# LVDS-Banana.net
KiCad netlist of a schematic drawn in EAGLE
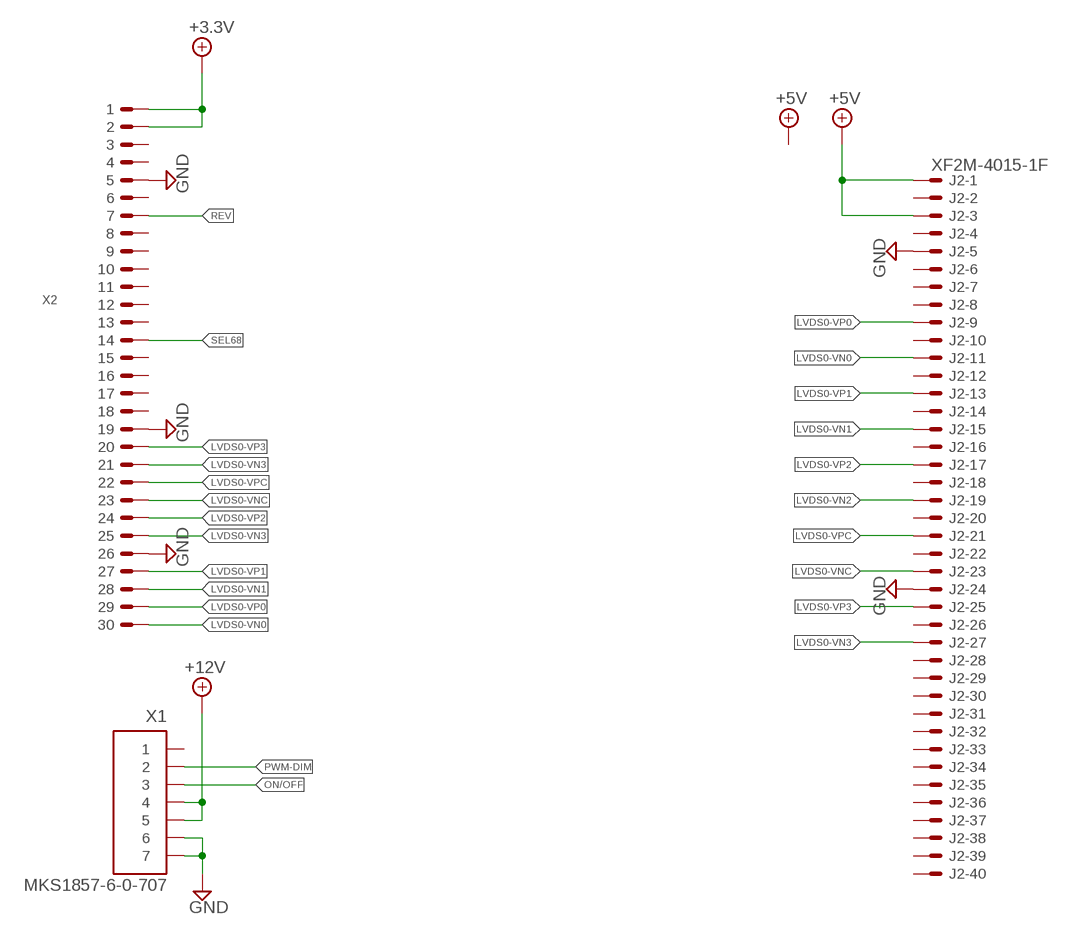
[diagram p0: schematic, sheet 1]

(export (version "E")
  (design (tool "Eeschema 10.0.6"))
  (components
    (comp (ref "J2")
      (value "XF2M-4015-1F")
      (footprint "eagle-import:XF2M-4015-1F")
      (libsource (lib "eagle-import") (part "XF2-40?15-1FM"))
    )
    (comp (ref "X1")
      (value "MKS1857-6-0-707")
      (footprint "eagle-import:MKS1857-6-0-707")
      (libsource (lib "eagle-import") (part "MKS1857-6-0-707"))
    )
    (comp (ref "X2")
      (value "DF14-30P-1.25H")
      (footprint "eagle-import:DF14-30")
      (libsource (lib "eagle-import") (part "DF14-30P-1.25H"))
    )
  )
  (nets
    (net (code "1") (name "+3.3V") (class "Default")
      (node (ref "X2") (pin "1") (pinfunction "1_1") (pintype "passive"))
      (node (ref "X2") (pin "2") (pinfunction "2_2") (pintype "passive"))
    )
    (net (code "2") (name "+5V") (class "Default")
      (node (ref "J2") (pin "1") (pinfunction "MSV_1") (pintype "passive"))
      (node (ref "J2") (pin "3") (pinfunction "MS_3") (pintype "passive"))
    )
    (net (code "3") (name "+12V") (class "Default")
      (node (ref "X1") (pin "4") (pinfunction "4_4") (pintype "input"))
      (node (ref "X1") (pin "5") (pinfunction "5_5") (pintype "input"))
    )
    (net (code "4") (name "GND") (class "Default")
      (node (ref "J2") (pin "24") (pinfunction "MS_24") (pintype "passive"))
      (node (ref "J2") (pin "5") (pinfunction "MS_5") (pintype "passive"))
      (node (ref "X1") (pin "6") (pinfunction "6_6") (pintype "input"))
      (node (ref "X1") (pin "7") (pinfunction "7_7") (pintype "input"))
      (node (ref "X2") (pin "19") (pinfunction "19_19") (pintype "passive"))
      (node (ref "X2") (pin "26") (pinfunction "26_26") (pintype "passive"))
      (node (ref "X2") (pin "5") (pinfunction "5_5") (pintype "passive"))
    )
    (net (code "5") (name "LVDS0-VN0") (class "Default")
      (node (ref "J2") (pin "11") (pinfunction "MS_11") (pintype "passive"))
      (node (ref "X2") (pin "30") (pinfunction "30_30") (pintype "passive"))
    )
    (net (code "6") (name "LVDS0-VN1") (class "Default")
      (node (ref "J2") (pin "15") (pinfunction "MS_15") (pintype "passive"))
      (node (ref "X2") (pin "28") (pinfunction "28_28") (pintype "passive"))
    )
    (net (code "7") (name "LVDS0-VN2") (class "Default")
      (node (ref "J2") (pin "19") (pinfunction "MS_19") (pintype "passive"))
    )
    (net (code "8") (name "LVDS0-VN3") (class "Default")
      (node (ref "J2") (pin "27") (pinfunction "MS_27") (pintype "passive"))
      (node (ref "X2") (pin "21") (pinfunction "21_21") (pintype "passive"))
      (node (ref "X2") (pin "25") (pinfunction "25_25") (pintype "passive"))
    )
    (net (code "9") (name "LVDS0-VNC") (class "Default")
      (node (ref "J2") (pin "23") (pinfunction "MS_23") (pintype "passive"))
      (node (ref "X2") (pin "23") (pinfunction "23_23") (pintype "passive"))
    )
    (net (code "10") (name "LVDS0-VP0") (class "Default")
      (node (ref "J2") (pin "9") (pinfunction "MS_9") (pintype "passive"))
      (node (ref "X2") (pin "29") (pinfunction "29_29") (pintype "passive"))
    )
    (net (code "11") (name "LVDS0-VP1") (class "Default")
      (node (ref "J2") (pin "13") (pinfunction "MS_13") (pintype "passive"))
      (node (ref "X2") (pin "27") (pinfunction "27_27") (pintype "passive"))
    )
    (net (code "12") (name "LVDS0-VP2") (class "Default")
      (node (ref "J2") (pin "17") (pinfunction "MS_17") (pintype "passive"))
      (node (ref "X2") (pin "24") (pinfunction "24_24") (pintype "passive"))
    )
    (net (code "13") (name "LVDS0-VP3") (class "Default")
      (node (ref "J2") (pin "25") (pinfunction "MS_25") (pintype "passive"))
      (node (ref "X2") (pin "20") (pinfunction "20_20") (pintype "passive"))
    )
    (net (code "14") (name "LVDS0-VPC") (class "Default")
      (node (ref "J2") (pin "21") (pinfunction "MS_21") (pintype "passive"))
      (node (ref "X2") (pin "22") (pinfunction "22_22") (pintype "passive"))
    )
    (net (code "15") (name "ON{slash}OFF") (class "Default")
      (node (ref "X1") (pin "3") (pinfunction "3_3") (pintype "input"))
    )
    (net (code "16") (name "PWM-DIM") (class "Default")
      (node (ref "X1") (pin "2") (pinfunction "2_2") (pintype "input"))
    )
    (net (code "17") (name "REV") (class "Default")
      (node (ref "X2") (pin "7") (pinfunction "7_7") (pintype "passive"))
    )
    (net (code "18") (name "SEL68") (class "Default")
      (node (ref "X2") (pin "14") (pinfunction "14_14") (pintype "passive"))
    )
    (net (code "19") (name "unconnected-(J2AA-MS-Pad33)") (class "Default")
      (node (ref "J2") (pin "33") (pinfunction "MS_33") (pintype "passive"))
    )
    (net (code "20") (name "unconnected-(J2AB-MS-Pad34)") (class "Default")
      (node (ref "J2") (pin "34") (pinfunction "MS_34") (pintype "passive"))
    )
    (net (code "21") (name "unconnected-(J2AC-MS-Pad35)") (class "Default")
      (node (ref "J2") (pin "35") (pinfunction "MS_35") (pintype "passive"))
    )
    (net (code "22") (name "unconnected-(J2AD-MS-Pad36)") (class "Default")
      (node (ref "J2") (pin "36") (pinfunction "MS_36") (pintype "passive"))
    )
    (net (code "23") (name "unconnected-(J2AE-MS-Pad37)") (class "Default")
      (node (ref "J2") (pin "37") (pinfunction "MS_37") (pintype "passive"))
    )
    (net (code "24") (name "unconnected-(J2AF-MS-Pad38)") (class "Default")
      (node (ref "J2") (pin "38") (pinfunction "MS_38") (pintype "passive"))
    )
    (net (code "25") (name "unconnected-(J2AG-MS-Pad39)") (class "Default")
      (node (ref "J2") (pin "39") (pinfunction "MS_39") (pintype "passive"))
    )
    (net (code "26") (name "unconnected-(J2AH-MS-Pad4)") (class "Default")
      (node (ref "J2") (pin "4") (pinfunction "MS_4") (pintype "passive"))
    )
    (net (code "27") (name "unconnected-(J2AI-MS-Pad40)") (class "Default")
      (node (ref "J2") (pin "40") (pinfunction "MS_40") (pintype "passive"))
    )
    (net (code "28") (name "unconnected-(J2AK-MS-Pad6)") (class "Default")
      (node (ref "J2") (pin "6") (pinfunction "MS_6") (pintype "passive"))
    )
    (net (code "29") (name "unconnected-(J2AL-MS-Pad7)") (class "Default")
      (node (ref "J2") (pin "7") (pinfunction "MS_7") (pintype "passive"))
    )
    (net (code "30") (name "unconnected-(J2AM-MS-Pad8)") (class "Default")
      (node (ref "J2") (pin "8") (pinfunction "MS_8") (pintype "passive"))
    )
    (net (code "31") (name "unconnected-(J2B-MS-Pad10)") (class "Default")
      (node (ref "J2") (pin "10") (pinfunction "MS_10") (pintype "passive"))
    )
    (net (code "32") (name "unconnected-(J2D-MS-Pad12)") (class "Default")
      (node (ref "J2") (pin "12") (pinfunction "MS_12") (pintype "passive"))
    )
    (net (code "33") (name "unconnected-(J2F-MS-Pad14)") (class "Default")
      (node (ref "J2") (pin "14") (pinfunction "MS_14") (pintype "passive"))
    )
    (net (code "34") (name "unconnected-(J2H-MS-Pad16)") (class "Default")
      (node (ref "J2") (pin "16") (pinfunction "MS_16") (pintype "passive"))
    )
    (net (code "35") (name "unconnected-(J2J-MS-Pad18)") (class "Default")
      (node (ref "J2") (pin "18") (pinfunction "MS_18") (pintype "passive"))
    )
    (net (code "36") (name "unconnected-(J2L-MS-Pad2)") (class "Default")
      (node (ref "J2") (pin "2") (pinfunction "MS_2") (pintype "passive"))
    )
    (net (code "37") (name "unconnected-(J2M-MS-Pad20)") (class "Default")
      (node (ref "J2") (pin "20") (pinfunction "MS_20") (pintype "passive"))
    )
    (net (code "38") (name "unconnected-(J2O-MS-Pad22)") (class "Default")
      (node (ref "J2") (pin "22") (pinfunction "MS_22") (pintype "passive"))
    )
    (net (code "39") (name "unconnected-(J2S-MS-Pad26)") (class "Default")
      (node (ref "J2") (pin "26") (pinfunction "MS_26") (pintype "passive"))
    )
    (net (code "40") (name "unconnected-(J2U-MS-Pad28)") (class "Default")
      (node (ref "J2") (pin "28") (pinfunction "MS_28") (pintype "passive"))
    )
    (net (code "41") (name "unconnected-(J2V-MS-Pad29)") (class "Default")
      (node (ref "J2") (pin "29") (pinfunction "MS_29") (pintype "passive"))
    )
    (net (code "42") (name "unconnected-(J2X-MS-Pad30)") (class "Default")
      (node (ref "J2") (pin "30") (pinfunction "MS_30") (pintype "passive"))
    )
    (net (code "43") (name "unconnected-(J2Y-MS-Pad31)") (class "Default")
      (node (ref "J2") (pin "31") (pinfunction "MS_31") (pintype "passive"))
    )
    (net (code "44") (name "unconnected-(J2Z-MS-Pad32)") (class "Default")
      (node (ref "J2") (pin "32") (pinfunction "MS_32") (pintype "passive"))
    )
    (net (code "45") (name "unconnected-(X1-Pad1)") (class "Default")
      (node (ref "X1") (pin "1") (pinfunction "1_1") (pintype "input"))
    )
    (net (code "46") (name "unconnected-(X2-Pad3)") (class "Default")
      (node (ref "X2") (pin "3") (pinfunction "3_3") (pintype "passive"))
    )
    (net (code "47") (name "unconnected-(X2-Pad4)") (class "Default")
      (node (ref "X2") (pin "4") (pinfunction "4_4") (pintype "passive"))
    )
    (net (code "48") (name "unconnected-(X2-Pad6)") (class "Default")
      (node (ref "X2") (pin "6") (pinfunction "6_6") (pintype "passive"))
    )
    (net (code "49") (name "unconnected-(X2-Pad8)") (class "Default")
      (node (ref "X2") (pin "8") (pinfunction "8_8") (pintype "passive"))
    )
    (net (code "50") (name "unconnected-(X2-Pad9)") (class "Default")
      (node (ref "X2") (pin "9") (pinfunction "9_9") (pintype "passive"))
    )
    (net (code "51") (name "unconnected-(X2-Pad10)") (class "Default")
      (node (ref "X2") (pin "10") (pinfunction "10_10") (pintype "passive"))
    )
    (net (code "52") (name "unconnected-(X2-Pad11)") (class "Default")
      (node (ref "X2") (pin "11") (pinfunction "11_11") (pintype "passive"))
    )
    (net (code "53") (name "unconnected-(X2-Pad12)") (class "Default")
      (node (ref "X2") (pin "12") (pinfunction "12_12") (pintype "passive"))
    )
    (net (code "54") (name "unconnected-(X2-Pad13)") (class "Default")
      (node (ref "X2") (pin "13") (pinfunction "13_13") (pintype "passive"))
    )
    (net (code "55") (name "unconnected-(X2-Pad15)") (class "Default")
      (node (ref "X2") (pin "15") (pinfunction "15_15") (pintype "passive"))
    )
    (net (code "56") (name "unconnected-(X2-Pad16)") (class "Default")
      (node (ref "X2") (pin "16") (pinfunction "16_16") (pintype "passive"))
    )
    (net (code "57") (name "unconnected-(X2-Pad17)") (class "Default")
      (node (ref "X2") (pin "17") (pinfunction "17_17") (pintype "passive"))
    )
    (net (code "58") (name "unconnected-(X2-Pad18)") (class "Default")
      (node (ref "X2") (pin "18") (pinfunction "18_18") (pintype "passive"))
    )
  )
)
